# e-208_bms_master_v2.net
KiCad netlist of a schematic drawn in EAGLE
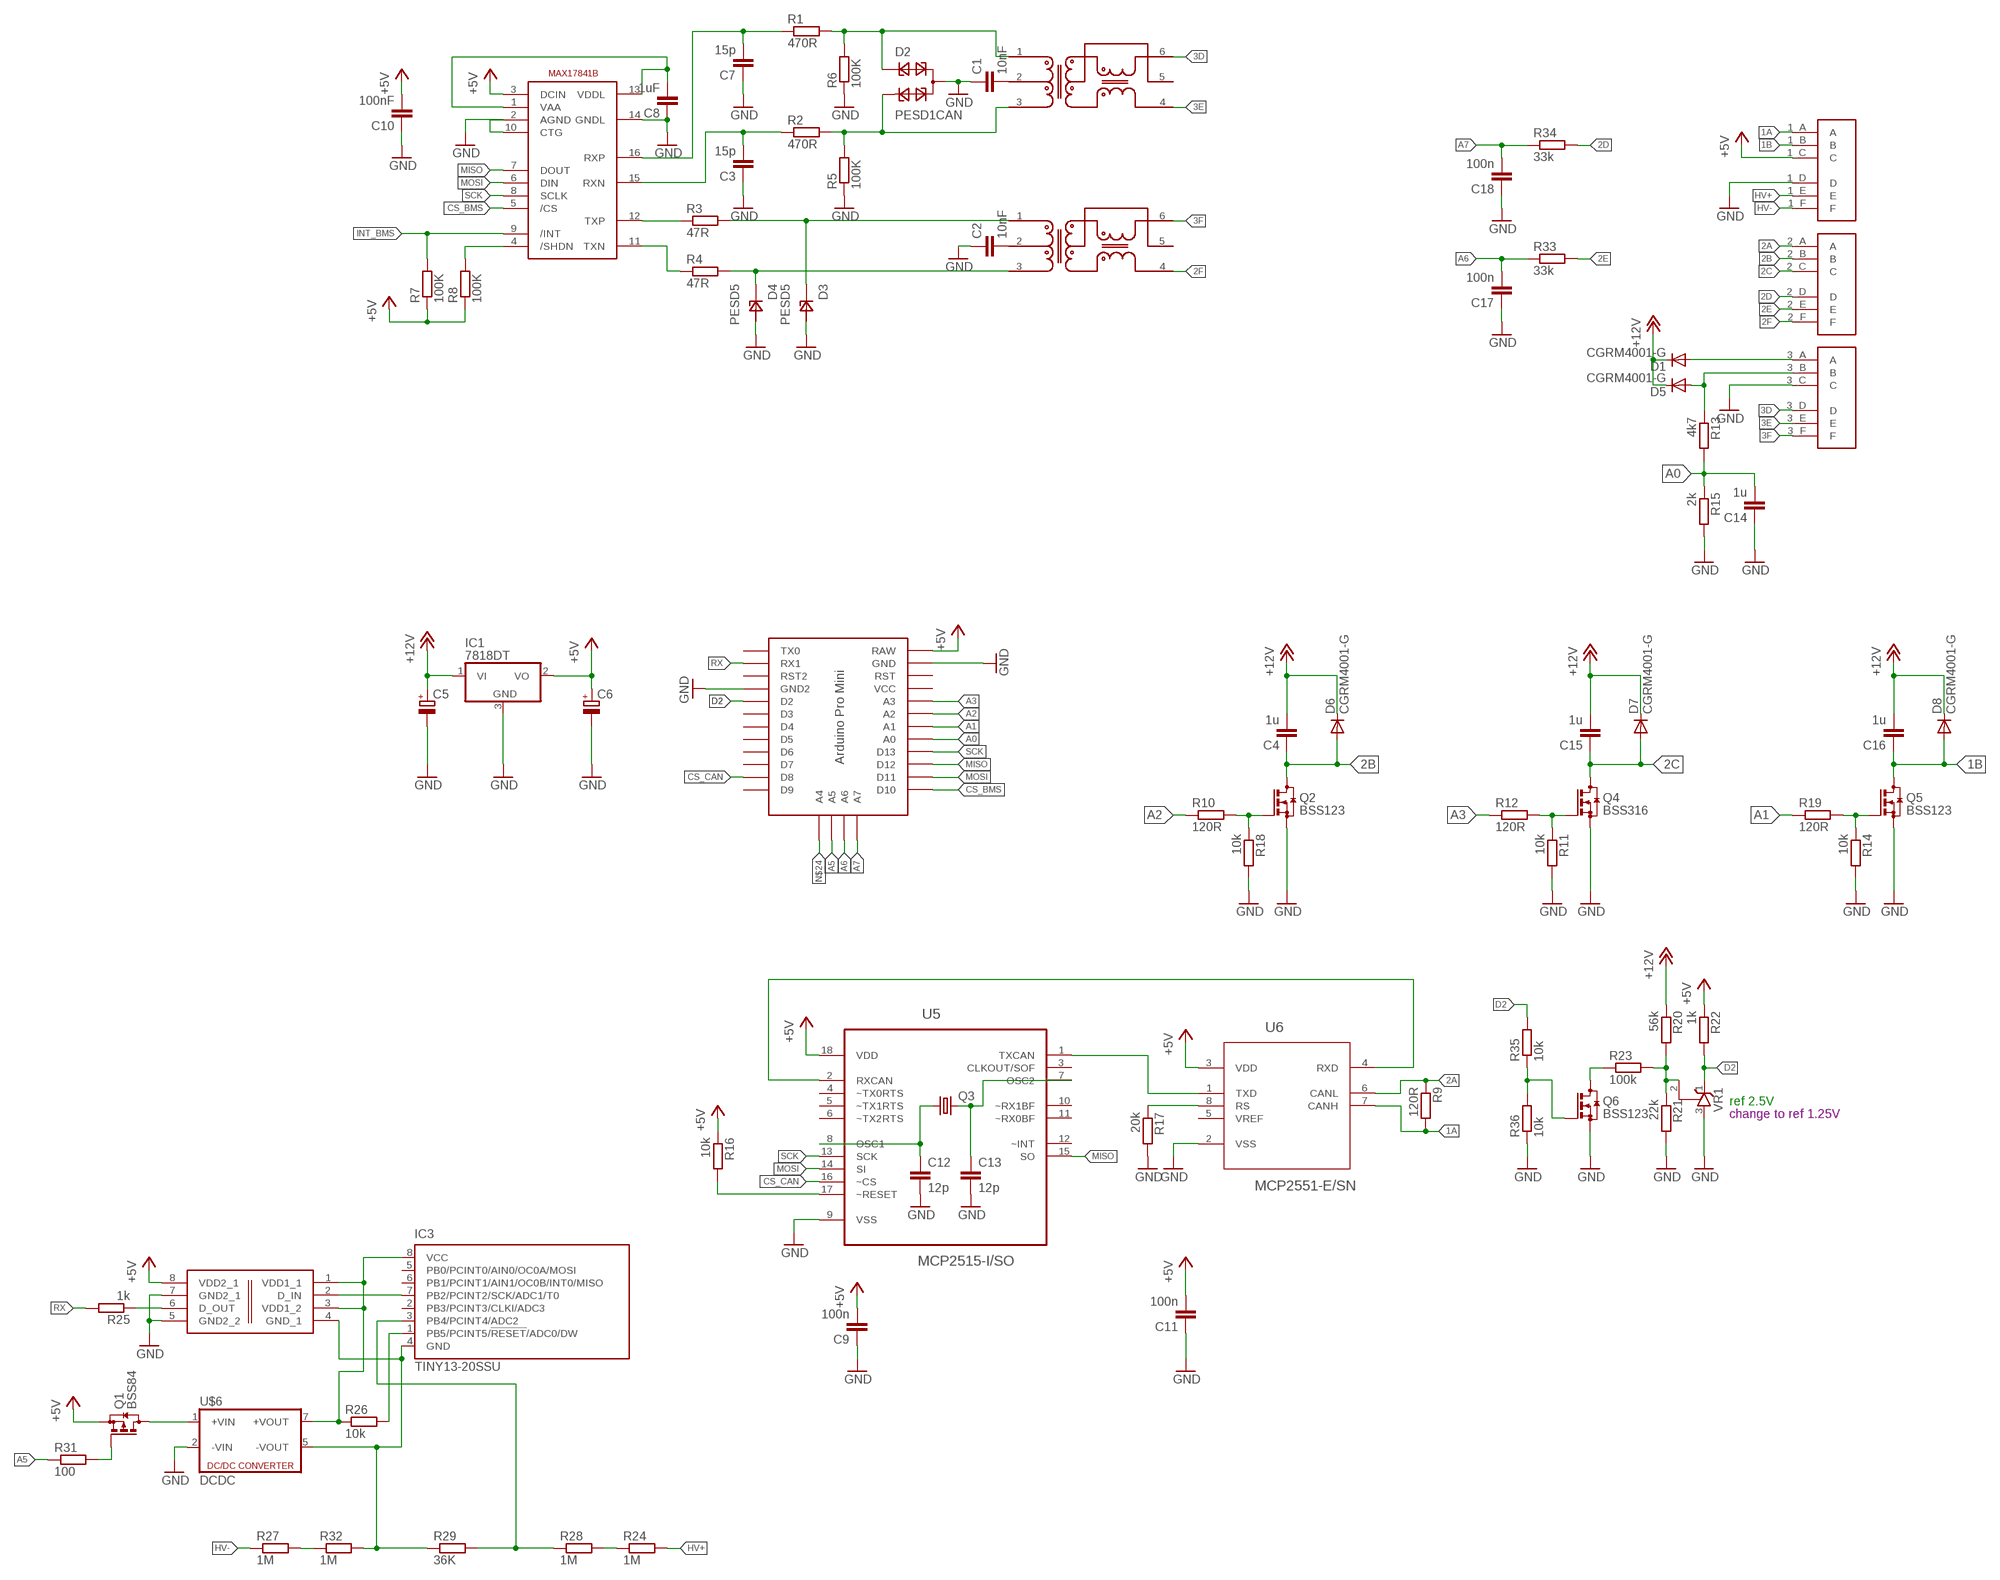
[diagram p0: schematic, sheet 1]

(export (version "E")
  (design (tool "Eeschema 10.0.6"))
  (components
    (comp (ref "C1")
      (value "10nF")
      (footprint "eagle-import:C0805")
      (libsource (lib "eagle-import") (part "C-EUC0805"))
    )
    (comp (ref "C2")
      (value "10nF")
      (footprint "eagle-import:C0805")
      (libsource (lib "eagle-import") (part "C-EUC0805"))
    )
    (comp (ref "C3")
      (value "15p")
      (footprint "eagle-import:C0805")
      (libsource (lib "eagle-import") (part "C-EUC0805"))
    )
    (comp (ref "C4")
      (value "1u")
      (footprint "eagle-import:C0805")
      (libsource (lib "eagle-import") (part "C-EUC0805"))
    )
    (comp (ref "C5")
      (value "CPOL-EU153CLV-1010")
      (footprint "eagle-import:153CLV-1010")
      (libsource (lib "eagle-import") (part "CPOL-EU153CLV-1010"))
    )
    (comp (ref "C6")
      (value "CPOL-EU153CLV-1010")
      (footprint "eagle-import:153CLV-1010")
      (libsource (lib "eagle-import") (part "CPOL-EU153CLV-1010"))
    )
    (comp (ref "C7")
      (value "15p")
      (footprint "eagle-import:C0805")
      (libsource (lib "eagle-import") (part "C-EUC0805"))
    )
    (comp (ref "C8")
      (value "1uF")
      (footprint "eagle-import:C0805")
      (libsource (lib "eagle-import") (part "C-EUC0805"))
    )
    (comp (ref "C9")
      (value "100n")
      (footprint "eagle-import:C0805")
      (libsource (lib "eagle-import") (part "C-EUC0805"))
    )
    (comp (ref "C10")
      (value "100nF")
      (footprint "eagle-import:C0805")
      (libsource (lib "eagle-import") (part "C-EUC0805"))
    )
    (comp (ref "C11")
      (value "100n")
      (footprint "eagle-import:C0805")
      (libsource (lib "eagle-import") (part "C-EUC0805"))
    )
    (comp (ref "C12")
      (value "12p")
      (footprint "eagle-import:C0603")
      (libsource (lib "eagle-import") (part "C-EUC0603"))
    )
    (comp (ref "C13")
      (value "12p")
      (footprint "eagle-import:C0603")
      (libsource (lib "eagle-import") (part "C-EUC0603"))
    )
    (comp (ref "C14")
      (value "1u")
      (footprint "eagle-import:C0805")
      (libsource (lib "eagle-import") (part "C-EUC0805"))
    )
    (comp (ref "C15")
      (value "1u")
      (footprint "eagle-import:C0805")
      (libsource (lib "eagle-import") (part "C-EUC0805"))
    )
    (comp (ref "C16")
      (value "1u")
      (footprint "eagle-import:C0805")
      (libsource (lib "eagle-import") (part "C-EUC0805"))
    )
    (comp (ref "C17")
      (value "100n")
      (footprint "eagle-import:C0805")
      (libsource (lib "eagle-import") (part "C-EUC0805"))
    )
    (comp (ref "C18")
      (value "100n")
      (footprint "eagle-import:C0805")
      (libsource (lib "eagle-import") (part "C-EUC0805"))
    )
    (comp (ref "D1")
      (value "CGRM4001-G")
      (footprint "eagle-import:SOD-123_MINI-SMA")
      (libsource (lib "eagle-import") (part "CGRM400-G1"))
    )
    (comp (ref "D2")
      (value "PESD1CAN")
      (footprint "eagle-import:SOT23")
      (libsource (lib "eagle-import") (part "PESD1CAN"))
    )
    (comp (ref "D3")
      (value "PESD5")
      (footprint "eagle-import:SOD323")
      (libsource (lib "eagle-import") (part "PESD5"))
    )
    (comp (ref "D4")
      (value "PESD5")
      (footprint "eagle-import:SOD323")
      (libsource (lib "eagle-import") (part "PESD5"))
    )
    (comp (ref "D5")
      (value "CGRM4001-G")
      (footprint "eagle-import:SOD-123_MINI-SMA")
      (libsource (lib "eagle-import") (part "CGRM400-G1"))
    )
    (comp (ref "D6")
      (value "CGRM4001-G")
      (footprint "eagle-import:SOD-123_MINI-SMA")
      (libsource (lib "eagle-import") (part "CGRM400-G1"))
    )
    (comp (ref "D7")
      (value "CGRM4001-G")
      (footprint "eagle-import:SOD-123_MINI-SMA")
      (libsource (lib "eagle-import") (part "CGRM400-G1"))
    )
    (comp (ref "D8")
      (value "CGRM4001-G")
      (footprint "eagle-import:SOD-123_MINI-SMA")
      (libsource (lib "eagle-import") (part "CGRM400-G1"))
    )
    (comp (ref "IC1")
      (value "7818DT")
      (footprint "eagle-import:TO252")
      (libsource (lib "eagle-import") (part "78DT18"))
    )
    (comp (ref "IC3")
      (value "TINY13-20SSU")
      (footprint "eagle-import:8S1")
      (fields (field (name "MPN") "ATTINY13-20SSU"))
      (libsource (lib "eagle-import") (part "TINY13SSU-20"))
    )
    (comp (ref "Q1")
      (value "BSS84")
      (footprint "eagle-import:SOT23")
      (libsource (lib "eagle-import") (part "BSS84"))
    )
    (comp (ref "Q2")
      (value "BSS123")
      (footprint "eagle-import:SOT23")
      (libsource (lib "eagle-import") (part "BSS123"))
    )
    (comp (ref "Q3")
      (value "CRYSTALHC49U-V")
      (footprint "eagle-import:HC49U-V")
      (libsource (lib "eagle-import") (part "CRYSTALHC49U-V"))
    )
    (comp (ref "Q4")
      (value "BSS316")
      (footprint "eagle-import:SOT23")
      (libsource (lib "eagle-import") (part "BSS123"))
    )
    (comp (ref "Q5")
      (value "BSS123")
      (footprint "eagle-import:SOT23")
      (libsource (lib "eagle-import") (part "BSS123"))
    )
    (comp (ref "Q6")
      (value "BSS123")
      (footprint "eagle-import:SOT23")
      (libsource (lib "eagle-import") (part "BSS123"))
    )
    (comp (ref "R1")
      (value "470R")
      (footprint "eagle-import:R0805")
      (libsource (lib "eagle-import") (part "R-EU_R0805"))
    )
    (comp (ref "R2")
      (value "470R")
      (footprint "eagle-import:R0805")
      (libsource (lib "eagle-import") (part "R-EU_R0805"))
    )
    (comp (ref "R3")
      (value "47R")
      (footprint "eagle-import:R0805")
      (libsource (lib "eagle-import") (part "R-EU_R0805"))
    )
    (comp (ref "R4")
      (value "47R")
      (footprint "eagle-import:R0805")
      (libsource (lib "eagle-import") (part "R-EU_R0805"))
    )
    (comp (ref "R5")
      (value "100K")
      (footprint "eagle-import:R0805")
      (libsource (lib "eagle-import") (part "R-EU_R0805"))
    )
    (comp (ref "R6")
      (value "100K")
      (footprint "eagle-import:R0805")
      (libsource (lib "eagle-import") (part "R-EU_R0805"))
    )
    (comp (ref "R7")
      (value "100K")
      (footprint "eagle-import:R0805")
      (libsource (lib "eagle-import") (part "R-EU_R0805"))
    )
    (comp (ref "R8")
      (value "100K")
      (footprint "eagle-import:R0805")
      (libsource (lib "eagle-import") (part "R-EU_R0805"))
    )
    (comp (ref "R9")
      (value "120R")
      (footprint "eagle-import:R0805")
      (libsource (lib "eagle-import") (part "R-EU_R0805"))
    )
    (comp (ref "R10")
      (value "120R")
      (footprint "eagle-import:R0805")
      (libsource (lib "eagle-import") (part "R-EU_R0805"))
    )
    (comp (ref "R11")
      (value "10k")
      (footprint "eagle-import:R0805")
      (libsource (lib "eagle-import") (part "R-EU_R0805"))
    )
    (comp (ref "R12")
      (value "120R")
      (footprint "eagle-import:R0805")
      (libsource (lib "eagle-import") (part "R-EU_R0805"))
    )
    (comp (ref "R13")
      (value "4k7")
      (footprint "eagle-import:R0805")
      (libsource (lib "eagle-import") (part "R-EU_R0805"))
    )
    (comp (ref "R14")
      (value "10k")
      (footprint "eagle-import:R0805")
      (libsource (lib "eagle-import") (part "R-EU_R0805"))
    )
    (comp (ref "R15")
      (value "2k")
      (footprint "eagle-import:R0805")
      (libsource (lib "eagle-import") (part "R-EU_R0805"))
    )
    (comp (ref "R16")
      (value "10k")
      (footprint "eagle-import:R0805")
      (libsource (lib "eagle-import") (part "R-EU_R0805"))
    )
    (comp (ref "R17")
      (value "20k")
      (footprint "eagle-import:R0805")
      (libsource (lib "eagle-import") (part "R-EU_R0805"))
    )
    (comp (ref "R18")
      (value "10k")
      (footprint "eagle-import:R0805")
      (libsource (lib "eagle-import") (part "R-EU_R0805"))
    )
    (comp (ref "R19")
      (value "120R")
      (footprint "eagle-import:R0805")
      (libsource (lib "eagle-import") (part "R-EU_R0805"))
    )
    (comp (ref "R20")
      (value "56k")
      (footprint "eagle-import:R0805")
      (libsource (lib "eagle-import") (part "R-EU_R0805"))
    )
    (comp (ref "R21")
      (value "22k")
      (footprint "eagle-import:R0805")
      (libsource (lib "eagle-import") (part "R-EU_R0805"))
    )
    (comp (ref "R22")
      (value "1k")
      (footprint "eagle-import:R0805")
      (libsource (lib "eagle-import") (part "R-EU_R0805"))
    )
    (comp (ref "R23")
      (value "100k")
      (footprint "eagle-import:R0805")
      (libsource (lib "eagle-import") (part "R-EU_R0805"))
    )
    (comp (ref "R24")
      (value "1M")
      (footprint "eagle-import:R0805")
      (libsource (lib "eagle-import") (part "R-EU_R0805"))
    )
    (comp (ref "R25")
      (value "1k")
      (footprint "eagle-import:R0805")
      (libsource (lib "eagle-import") (part "R-EU_R0805"))
    )
    (comp (ref "R26")
      (value "10k")
      (footprint "eagle-import:R0805")
      (libsource (lib "eagle-import") (part "R-EU_R0805"))
    )
    (comp (ref "R27")
      (value "1M")
      (footprint "eagle-import:R0805")
      (libsource (lib "eagle-import") (part "R-EU_R0805"))
    )
    (comp (ref "R28")
      (value "1M")
      (footprint "eagle-import:R0805")
      (libsource (lib "eagle-import") (part "R-EU_R0805"))
    )
    (comp (ref "R29")
      (value "36K")
      (footprint "eagle-import:R0805")
      (libsource (lib "eagle-import") (part "R-EU_R0805"))
    )
    (comp (ref "R31")
      (value "100")
      (footprint "eagle-import:R0805")
      (libsource (lib "eagle-import") (part "R-EU_R0805"))
    )
    (comp (ref "R32")
      (value "1M")
      (footprint "eagle-import:R0805")
      (libsource (lib "eagle-import") (part "R-EU_R0805"))
    )
    (comp (ref "R33")
      (value "33k")
      (footprint "eagle-import:R0805")
      (libsource (lib "eagle-import") (part "R-EU_R0805"))
    )
    (comp (ref "R34")
      (value "33k")
      (footprint "eagle-import:R0805")
      (libsource (lib "eagle-import") (part "R-EU_R0805"))
    )
    (comp (ref "R35")
      (value "10k")
      (footprint "eagle-import:R0805")
      (libsource (lib "eagle-import") (part "R-EU_R0805"))
    )
    (comp (ref "R36")
      (value "10k")
      (footprint "eagle-import:R0805")
      (libsource (lib "eagle-import") (part "R-EU_R0805"))
    )
    (comp (ref "U$1")
      (value "18P_ME")
      (footprint "eagle-import:18P_ME")
      (libsource (lib "eagle-import") (part "18P_ME"))
    )
    (comp (ref "U$2")
      (value "PRO-MINI-3")
      (footprint "eagle-import:PRO-MINI-3")
      (libsource (lib "eagle-import") (part "PRO-MINI-3"))
    )
    (comp (ref "U$3")
      (value "SM91502ALE")
      (footprint "eagle-import:SM91502ALE")
      (libsource (lib "eagle-import") (part "SM91502ALE"))
    )
    (comp (ref "U$4")
      (value "SM91502ALE")
      (footprint "eagle-import:SM91502ALE")
      (libsource (lib "eagle-import") (part "SM91502ALE"))
    )
    (comp (ref "U$5")
      (value "ADUM110N")
      (footprint "eagle-import:SOIC8")
      (libsource (lib "eagle-import") (part "ADUM110N"))
    )
    (comp (ref "U$6")
      (value "DCDC")
      (footprint "eagle-import:DCDC")
      (libsource (lib "eagle-import") (part "DCDC"))
    )
    (comp (ref "U2")
      (value "MAX17841B")
      (footprint "eagle-import:TSSOP16")
      (libsource (lib "eagle-import") (part "MAX17841B"))
    )
    (comp (ref "U5")
      (value "MCP2515-I/SO")
      (footprint "eagle-import:SOIC127P1034X264-18N")
      (libsource (lib "eagle-import") (part "MCP2515-I/SO"))
    )
    (comp (ref "U6")
      (value "MCP2551-E/SN")
      (footprint "eagle-import:SOIC127P600X175-8N")
      (libsource (lib "eagle-import") (part "MCP2551-E/SN"))
    )
    (comp (ref "VR1")
      (value "TL431CLPSOT23")
      (footprint "eagle-import:SOT23")
      (libsource (lib "eagle-import") (part "TL431CLPSOT23"))
    )
  )
  (nets
    (net (code "1") (name "+5V") (class "Default")
      (node (ref "C10") (pin "2") (pinfunction "2_2") (pintype "passive"))
      (node (ref "C11") (pin "2") (pinfunction "2_2") (pintype "passive"))
      (node (ref "C6") (pin "+") (pinfunction "+_+") (pintype "passive"))
      (node (ref "C9") (pin "2") (pinfunction "2_2") (pintype "passive"))
      (node (ref "IC1") (pin "2") (pinfunction "VO_2") (pintype "passive"))
      (node (ref "Q1") (pin "2") (pinfunction "S_2") (pintype "passive"))
      (node (ref "R16") (pin "1") (pinfunction "1_1") (pintype "passive"))
      (node (ref "R22") (pin "1") (pinfunction "1_1") (pintype "passive"))
      (node (ref "R7") (pin "1") (pinfunction "1_1") (pintype "passive"))
      (node (ref "R8") (pin "1") (pinfunction "1_1") (pintype "passive"))
      (node (ref "U$1") (pin "1_C") (pinfunction "C_1_C") (pintype "bidirectional"))
      (node (ref "U$2") (pin "RAW") (pinfunction "RAW_RAW") (pintype "power_in"))
      (node (ref "U$5") (pin "8") (pinfunction "VDD2_1_8") (pintype "bidirectional"))
      (node (ref "U2") (pin "3") (pinfunction "DCIN_3") (pintype "bidirectional"))
      (node (ref "U5") (pin "18") (pinfunction "VDD_18") (pintype "power_in"))
      (node (ref "U6") (pin "3") (pinfunction "VDD_3") (pintype "power_in"))
    )
    (net (code "2") (name "+12V") (class "Default")
      (node (ref "C15") (pin "2") (pinfunction "2_2") (pintype "passive"))
      (node (ref "C16") (pin "2") (pinfunction "2_2") (pintype "passive"))
      (node (ref "C4") (pin "2") (pinfunction "2_2") (pintype "passive"))
      (node (ref "C5") (pin "+") (pinfunction "+_+") (pintype "passive"))
      (node (ref "D1") (pin "C") (pinfunction "C_C") (pintype "passive"))
      (node (ref "D5") (pin "C") (pinfunction "C_C") (pintype "passive"))
      (node (ref "D6") (pin "C") (pinfunction "C_C") (pintype "passive"))
      (node (ref "D7") (pin "C") (pinfunction "C_C") (pintype "passive"))
      (node (ref "D8") (pin "C") (pinfunction "C_C") (pintype "passive"))
      (node (ref "IC1") (pin "1") (pinfunction "VI_1") (pintype "input"))
      (node (ref "R20") (pin "1") (pinfunction "1_1") (pintype "passive"))
    )
    (net (code "3") (name "1A") (class "Default")
      (node (ref "R9") (pin "2") (pinfunction "2_2") (pintype "passive"))
      (node (ref "U$1") (pin "1_A") (pinfunction "A_1_A") (pintype "bidirectional"))
      (node (ref "U6") (pin "7") (pinfunction "CANH_7") (pintype "output"))
    )
    (net (code "4") (name "1B") (class "Default")
      (node (ref "C16") (pin "1") (pinfunction "1_1") (pintype "passive"))
      (node (ref "D8") (pin "A") (pinfunction "A_A") (pintype "passive"))
      (node (ref "Q5") (pin "3") (pinfunction "D_3") (pintype "passive"))
      (node (ref "U$1") (pin "1_B") (pinfunction "B_1_B") (pintype "bidirectional"))
    )
    (net (code "5") (name "2A") (class "Default")
      (node (ref "R9") (pin "1") (pinfunction "1_1") (pintype "passive"))
      (node (ref "U$1") (pin "2_A") (pinfunction "A_2_A") (pintype "bidirectional"))
      (node (ref "U6") (pin "6") (pinfunction "CANL_6") (pintype "output"))
    )
    (net (code "6") (name "2B") (class "Default")
      (node (ref "C4") (pin "1") (pinfunction "1_1") (pintype "passive"))
      (node (ref "D6") (pin "A") (pinfunction "A_A") (pintype "passive"))
      (node (ref "Q2") (pin "3") (pinfunction "D_3") (pintype "passive"))
      (node (ref "U$1") (pin "2_B") (pinfunction "B_2_B") (pintype "bidirectional"))
    )
    (net (code "7") (name "2C") (class "Default")
      (node (ref "C15") (pin "1") (pinfunction "1_1") (pintype "passive"))
      (node (ref "D7") (pin "A") (pinfunction "A_A") (pintype "passive"))
      (node (ref "Q4") (pin "3") (pinfunction "D_3") (pintype "passive"))
      (node (ref "U$1") (pin "2_C") (pinfunction "C_2_C") (pintype "bidirectional"))
    )
    (net (code "8") (name "2D") (class "Default")
      (node (ref "R34") (pin "2") (pinfunction "2_2") (pintype "passive"))
      (node (ref "U$1") (pin "2_D") (pinfunction "D_2_D") (pintype "bidirectional"))
    )
    (net (code "9") (name "2E") (class "Default")
      (node (ref "R33") (pin "2") (pinfunction "2_2") (pintype "passive"))
      (node (ref "U$1") (pin "2_E") (pinfunction "E_2_E") (pintype "bidirectional"))
    )
    (net (code "10") (name "2F") (class "Default")
      (node (ref "U$1") (pin "2_F") (pinfunction "F_2_F") (pintype "bidirectional"))
      (node (ref "U$4") (pin "4") (pinfunction "4_4") (pintype "bidirectional"))
    )
    (net (code "11") (name "3D") (class "Default")
      (node (ref "U$1") (pin "3_D") (pinfunction "D_3_D") (pintype "bidirectional"))
      (node (ref "U$3") (pin "6") (pinfunction "6_6") (pintype "bidirectional"))
    )
    (net (code "12") (name "3E") (class "Default")
      (node (ref "U$1") (pin "3_E") (pinfunction "E_3_E") (pintype "bidirectional"))
      (node (ref "U$3") (pin "4") (pinfunction "4_4") (pintype "bidirectional"))
    )
    (net (code "13") (name "3F") (class "Default")
      (node (ref "U$1") (pin "3_F") (pinfunction "F_3_F") (pintype "bidirectional"))
      (node (ref "U$4") (pin "6") (pinfunction "6_6") (pintype "bidirectional"))
    )
    (net (code "14") (name "A0") (class "Default")
      (node (ref "C14") (pin "2") (pinfunction "2_2") (pintype "passive"))
      (node (ref "R13") (pin "2") (pinfunction "2_2") (pintype "passive"))
      (node (ref "R15") (pin "1") (pinfunction "1_1") (pintype "passive"))
      (node (ref "U$2") (pin "A0") (pinfunction "A0_A0") (pintype "bidirectional"))
    )
    (net (code "15") (name "A1") (class "Default")
      (node (ref "R19") (pin "1") (pinfunction "1_1") (pintype "passive"))
      (node (ref "U$2") (pin "A1") (pinfunction "A1_A1") (pintype "bidirectional"))
    )
    (net (code "16") (name "A2") (class "Default")
      (node (ref "R10") (pin "1") (pinfunction "1_1") (pintype "passive"))
      (node (ref "U$2") (pin "A2") (pinfunction "A2_A2") (pintype "bidirectional"))
    )
    (net (code "17") (name "A3") (class "Default")
      (node (ref "R12") (pin "1") (pinfunction "1_1") (pintype "passive"))
      (node (ref "U$2") (pin "A3") (pinfunction "A3_A3") (pintype "bidirectional"))
    )
    (net (code "18") (name "A5") (class "Default")
      (node (ref "R31") (pin "1") (pinfunction "1_1") (pintype "passive"))
      (node (ref "U$2") (pin "A5") (pinfunction "A5_A5") (pintype "bidirectional"))
    )
    (net (code "19") (name "A6") (class "Default")
      (node (ref "C17") (pin "2") (pinfunction "2_2") (pintype "passive"))
      (node (ref "R33") (pin "1") (pinfunction "1_1") (pintype "passive"))
      (node (ref "U$2") (pin "A6") (pinfunction "A6_A6") (pintype "bidirectional"))
    )
    (net (code "20") (name "A7") (class "Default")
      (node (ref "C18") (pin "2") (pinfunction "2_2") (pintype "passive"))
      (node (ref "R34") (pin "1") (pinfunction "1_1") (pintype "passive"))
      (node (ref "U$2") (pin "A7") (pinfunction "A7_A7") (pintype "bidirectional"))
    )
    (net (code "21") (name "CS_BMS") (class "Default")
      (node (ref "U$2") (pin "D10") (pinfunction "D10_D10") (pintype "bidirectional"))
      (node (ref "U2") (pin "5") (pinfunction "/CS_5") (pintype "bidirectional"))
    )
    (net (code "22") (name "CS_CAN") (class "Default")
      (node (ref "U$2") (pin "D8") (pinfunction "D8_D8") (pintype "bidirectional"))
      (node (ref "U5") (pin "16") (pinfunction "~{CS}_16") (pintype "input"))
    )
    (net (code "23") (name "D2") (class "Default")
      (node (ref "R22") (pin "2") (pinfunction "2_2") (pintype "passive"))
      (node (ref "R35") (pin "2") (pinfunction "2_2") (pintype "passive"))
      (node (ref "U$2") (pin "D2") (pinfunction "D2_D2") (pintype "bidirectional"))
      (node (ref "VR1") (pin "1") (pinfunction "C_1") (pintype "passive"))
    )
    (net (code "24") (name "GND") (class "Default")
      (node (ref "C1") (pin "1") (pinfunction "1_1") (pintype "passive"))
      (node (ref "C10") (pin "1") (pinfunction "1_1") (pintype "passive"))
      (node (ref "C11") (pin "1") (pinfunction "1_1") (pintype "passive"))
      (node (ref "C12") (pin "2") (pinfunction "2_2") (pintype "passive"))
      (node (ref "C13") (pin "2") (pinfunction "2_2") (pintype "passive"))
      (node (ref "C14") (pin "1") (pinfunction "1_1") (pintype "passive"))
      (node (ref "C17") (pin "1") (pinfunction "1_1") (pintype "passive"))
      (node (ref "C18") (pin "1") (pinfunction "1_1") (pintype "passive"))
      (node (ref "C2") (pin "1") (pinfunction "1_1") (pintype "passive"))
      (node (ref "C3") (pin "1") (pinfunction "1_1") (pintype "passive"))
      (node (ref "C5") (pin "-") (pinfunction "-_-") (pintype "passive"))
      (node (ref "C6") (pin "-") (pinfunction "-_-") (pintype "passive"))
      (node (ref "C7") (pin "1") (pinfunction "1_1") (pintype "passive"))
      (node (ref "C8") (pin "1") (pinfunction "1_1") (pintype "passive"))
      (node (ref "C9") (pin "1") (pinfunction "1_1") (pintype "passive"))
      (node (ref "D2") (pin "3") (pinfunction "3_3") (pintype "passive"))
      (node (ref "D3") (pin "2") (pinfunction "2_2") (pintype "passive"))
      (node (ref "D4") (pin "2") (pinfunction "2_2") (pintype "passive"))
      (node (ref "IC1") (pin "3") (pinfunction "GND_3") (pintype "passive"))
      (node (ref "Q2") (pin "2") (pinfunction "S_2") (pintype "passive"))
      (node (ref "Q4") (pin "2") (pinfunction "S_2") (pintype "passive"))
      (node (ref "Q5") (pin "2") (pinfunction "S_2") (pintype "passive"))
      (node (ref "Q6") (pin "2") (pinfunction "S_2") (pintype "passive"))
      (node (ref "R11") (pin "2") (pinfunction "2_2") (pintype "passive"))
      (node (ref "R14") (pin "2") (pinfunction "2_2") (pintype "passive"))
      (node (ref "R15") (pin "2") (pinfunction "2_2") (pintype "passive"))
      (node (ref "R17") (pin "2") (pinfunction "2_2") (pintype "passive"))
      (node (ref "R18") (pin "2") (pinfunction "2_2") (pintype "passive"))
      (node (ref "R21") (pin "2") (pinfunction "2_2") (pintype "passive"))
      (node (ref "R36") (pin "1") (pinfunction "1_1") (pintype "passive"))
      (node (ref "R5") (pin "1") (pinfunction "1_1") (pintype "passive"))
      (node (ref "R6") (pin "1") (pinfunction "1_1") (pintype "passive"))
      (node (ref "U$1") (pin "1_D") (pinfunction "D_1_D") (pintype "bidirectional"))
      (node (ref "U$1") (pin "3_C") (pinfunction "C_3_C") (pintype "bidirectional"))
      (node (ref "U$2") (pin "GND") (pinfunction "GND_GND") (pintype "input"))
      (node (ref "U$2") (pin "GND1") (pinfunction "GND2_GND1") (pintype "bidirectional"))
      (node (ref "U$5") (pin "5") (pinfunction "GND2_2_5") (pintype "bidirectional"))
      (node (ref "U$5") (pin "7") (pinfunction "GND2_1_7") (pintype "bidirectional"))
      (node (ref "U$6") (pin "2") (pinfunction "-VIN_2") (pintype "passive"))
      (node (ref "U2") (pin "10") (pinfunction "CTG_10") (pintype "bidirectional"))
      (node (ref "U2") (pin "14") (pinfunction "GNDL_14") (pintype "bidirectional"))
      (node (ref "U2") (pin "2") (pinfunction "AGND_2") (pintype "bidirectional"))
      (node (ref "U5") (pin "9") (pinfunction "VSS_9") (pintype "power_in"))
      (node (ref "U6") (pin "2") (pinfunction "VSS_2") (pintype "power_in"))
      (node (ref "VR1") (pin "3") (pinfunction "A_3") (pintype "passive"))
    )
    (net (code "25") (name "HV+") (class "Default")
      (node (ref "R24") (pin "2") (pinfunction "2_2") (pintype "passive"))
      (node (ref "U$1") (pin "1_E") (pinfunction "E_1_E") (pintype "bidirectional"))
    )
    (net (code "26") (name "HV-") (class "Default")
      (node (ref "R27") (pin "1") (pinfunction "1_1") (pintype "passive"))
      (node (ref "U$1") (pin "1_F") (pinfunction "F_1_F") (pintype "bidirectional"))
    )
    (net (code "27") (name "INT_BMS") (class "Default")
      (node (ref "R7") (pin "2") (pinfunction "2_2") (pintype "passive"))
      (node (ref "U2") (pin "9") (pinfunction "/INT_9") (pintype "bidirectional"))
    )
    (net (code "28") (name "MISO") (class "Default")
      (node (ref "U$2") (pin "D12") (pinfunction "D12_D12") (pintype "bidirectional"))
      (node (ref "U2") (pin "7") (pinfunction "DOUT_7") (pintype "bidirectional"))
      (node (ref "U5") (pin "15") (pinfunction "SO_15") (pintype "output"))
    )
    (net (code "29") (name "MOSI") (class "Default")
      (node (ref "U$2") (pin "D11") (pinfunction "D11_D11") (pintype "bidirectional"))
      (node (ref "U2") (pin "6") (pinfunction "DIN_6") (pintype "bidirectional"))
      (node (ref "U5") (pin "14") (pinfunction "SI_14") (pintype "input"))
    )
    (net (code "30") (name "N$24") (class "Default")
      (node (ref "U$2") (pin "A4") (pinfunction "A4_A4") (pintype "bidirectional"))
    )
    (net (code "31") (name "Net-(C1-Pad2)") (class "Default")
      (node (ref "C1") (pin "2") (pinfunction "2_2") (pintype "passive"))
      (node (ref "U$3") (pin "2") (pinfunction "2_2") (pintype "bidirectional"))
    )
    (net (code "32") (name "Net-(C2-Pad2)") (class "Default")
      (node (ref "C2") (pin "2") (pinfunction "2_2") (pintype "passive"))
      (node (ref "U$4") (pin "2") (pinfunction "2_2") (pintype "bidirectional"))
    )
    (net (code "33") (name "Net-(D2-Pad1)") (class "Default")
      (node (ref "D2") (pin "1") (pinfunction "1_1") (pintype "passive"))
      (node (ref "R1") (pin "2") (pinfunction "2_2") (pintype "passive"))
      (node (ref "R6") (pin "2") (pinfunction "2_2") (pintype "passive"))
      (node (ref "U$3") (pin "1") (pinfunction "1_1") (pintype "bidirectional"))
    )
    (net (code "34") (name "Net-(D2-Pad2)") (class "Default")
      (node (ref "D2") (pin "2") (pinfunction "2_2") (pintype "passive"))
      (node (ref "R2") (pin "2") (pinfunction "2_2") (pintype "passive"))
      (node (ref "R5") (pin "2") (pinfunction "2_2") (pintype "passive"))
      (node (ref "U$3") (pin "3") (pinfunction "3_3") (pintype "bidirectional"))
    )
    (net (code "35") (name "Net-(D3-Pad1)") (class "Default")
      (node (ref "D3") (pin "1") (pinfunction "1_1") (pintype "passive"))
      (node (ref "R3") (pin "2") (pinfunction "2_2") (pintype "passive"))
      (node (ref "U$4") (pin "1") (pinfunction "1_1") (pintype "bidirectional"))
    )
    (net (code "36") (name "Net-(D4-Pad1)") (class "Default")
      (node (ref "D4") (pin "1") (pinfunction "1_1") (pintype "passive"))
      (node (ref "R4") (pin "2") (pinfunction "2_2") (pintype "passive"))
      (node (ref "U$4") (pin "3") (pinfunction "3_3") (pintype "bidirectional"))
    )
    (net (code "37") (name "Net-(IC3-GND)") (class "Default")
      (node (ref "IC3") (pin "4") (pinfunction "GND_4") (pintype "power_in"))
      (node (ref "R29") (pin "1") (pinfunction "1_1") (pintype "passive"))
      (node (ref "R32") (pin "2") (pinfunction "2_2") (pintype "passive"))
      (node (ref "U$5") (pin "4") (pinfunction "GND_1_4") (pintype "bidirectional"))
      (node (ref "U$6") (pin "5") (pinfunction "-VOUT_5") (pintype "passive"))
    )
    (net (code "38") (name "Net-(IC3-PB2{slash}PCINT2{slash}SCK{slash}ADC1{slash}T0)") (class "Default")
      (node (ref "IC3") (pin "7") (pinfunction "PB2/PCINT2/SCK/ADC1/T0_7") (pintype "bidirectional"))
      (node (ref "U$5") (pin "2") (pinfunction "D_IN_2") (pintype "bidirectional"))
    )
    (net (code "39") (name "Net-(IC3-PB4{slash}PCINT4{slash}ADC2)") (class "Default")
      (node (ref "IC3") (pin "3") (pinfunction "PB4/PCINT4/ADC2_3") (pintype "bidirectional"))
      (node (ref "R28") (pin "1") (pinfunction "1_1") (pintype "passive"))
      (node (ref "R29") (pin "2") (pinfunction "2_2") (pintype "passive"))
    )
    (net (code "40") (name "Net-(IC3-PB5{slash}PCINT5{slash}~{RESET}{slash}ADC0{slash}DW)") (class "Default")
      (node (ref "IC3") (pin "1") (pinfunction "PB5/PCINT5/~{RESET}/ADC0/DW_1") (pintype "bidirectional"))
      (node (ref "R26") (pin "2") (pinfunction "2_2") (pintype "passive"))
    )
    (net (code "41") (name "Net-(IC3-VCC)") (class "Default")
      (node (ref "IC3") (pin "8") (pinfunction "VCC_8") (pintype "power_in"))
      (node (ref "R26") (pin "1") (pinfunction "1_1") (pintype "passive"))
      (node (ref "U$5") (pin "1") (pinfunction "VDD1_1_1") (pintype "bidirectional"))
      (node (ref "U$5") (pin "3") (pinfunction "VDD1_2_3") (pintype "bidirectional"))
      (node (ref "U$6") (pin "7") (pinfunction "+VOUT_7") (pintype "passive"))
    )
    (net (code "42") (name "Net-(Q1-D)") (class "Default")
      (node (ref "Q1") (pin "3") (pinfunction "D_3") (pintype "passive"))
      (node (ref "U$6") (pin "1") (pinfunction "+VIN_1") (pintype "passive"))
    )
    (net (code "43") (name "Net-(Q1-G)") (class "Default")
      (node (ref "Q1") (pin "1") (pinfunction "G_1") (pintype "passive"))
      (node (ref "R31") (pin "2") (pinfunction "2_2") (pintype "passive"))
    )
    (net (code "44") (name "Net-(Q2-G)") (class "Default")
      (node (ref "Q2") (pin "1") (pinfunction "G_1") (pintype "passive"))
      (node (ref "R10") (pin "2") (pinfunction "2_2") (pintype "passive"))
      (node (ref "R18") (pin "1") (pinfunction "1_1") (pintype "passive"))
    )
    (net (code "45") (name "Net-(Q4-G)") (class "Default")
      (node (ref "Q4") (pin "1") (pinfunction "G_1") (pintype "passive"))
      (node (ref "R11") (pin "1") (pinfunction "1_1") (pintype "passive"))
      (node (ref "R12") (pin "2") (pinfunction "2_2") (pintype "passive"))
    )
    (net (code "46") (name "Net-(Q5-G)") (class "Default")
      (node (ref "Q5") (pin "1") (pinfunction "G_1") (pintype "passive"))
      (node (ref "R14") (pin "1") (pinfunction "1_1") (pintype "passive"))
      (node (ref "R19") (pin "2") (pinfunction "2_2") (pintype "passive"))
    )
    (net (code "47") (name "Net-(Q6-D)") (class "Default")
      (node (ref "Q6") (pin "3") (pinfunction "D_3") (pintype "passive"))
      (node (ref "R23") (pin "1") (pinfunction "1_1") (pintype "passive"))
    )
    (net (code "48") (name "Net-(Q6-G)") (class "Default")
      (node (ref "Q6") (pin "1") (pinfunction "G_1") (pintype "passive"))
      (node (ref "R35") (pin "1") (pinfunction "1_1") (pintype "passive"))
      (node (ref "R36") (pin "2") (pinfunction "2_2") (pintype "passive"))
    )
    (net (code "49") (name "Net-(R24-Pad1)") (class "Default")
      (node (ref "R24") (pin "1") (pinfunction "1_1") (pintype "passive"))
      (node (ref "R28") (pin "2") (pinfunction "2_2") (pintype "passive"))
    )
    (net (code "50") (name "Net-(R27-Pad2)") (class "Default")
      (node (ref "R27") (pin "2") (pinfunction "2_2") (pintype "passive"))
      (node (ref "R32") (pin "1") (pinfunction "1_1") (pintype "passive"))
    )
    (net (code "51") (name "Net-(U$1C-A)") (class "Default")
      (node (ref "D1") (pin "A") (pinfunction "A_A") (pintype "passive"))
      (node (ref "U$1") (pin "3_A") (pinfunction "A_3_A") (pintype "bidirectional"))
    )
    (net (code "52") (name "Net-(U$1C-B)") (class "Default")
      (node (ref "D5") (pin "A") (pinfunction "A_A") (pintype "passive"))
      (node (ref "R13") (pin "1") (pinfunction "1_1") (pintype "passive"))
      (node (ref "U$1") (pin "3_B") (pinfunction "B_3_B") (pintype "bidirectional"))
    )
    (net (code "53") (name "Net-(U$5-D_OUT)") (class "Default")
      (node (ref "R25") (pin "1") (pinfunction "1_1") (pintype "passive"))
      (node (ref "U$5") (pin "6") (pinfunction "D_OUT_6") (pintype "bidirectional"))
    )
    (net (code "54") (name "Net-(U2-RXN)") (class "Default")
      (node (ref "C3") (pin "2") (pinfunction "2_2") (pintype "passive"))
      (node (ref "R2") (pin "1") (pinfunction "1_1") (pintype "passive"))
      (node (ref "U2") (pin "15") (pinfunction "RXN_15") (pintype "bidirectional"))
    )
    (net (code "55") (name "Net-(U2-RXP)") (class "Default")
      (node (ref "C7") (pin "2") (pinfunction "2_2") (pintype "passive"))
      (node (ref "R1") (pin "1") (pinfunction "1_1") (pintype "passive"))
      (node (ref "U2") (pin "16") (pinfunction "RXP_16") (pintype "bidirectional"))
    )
    (net (code "56") (name "Net-(U2-TXN)") (class "Default")
      (node (ref "R4") (pin "1") (pinfunction "1_1") (pintype "passive"))
      (node (ref "U2") (pin "11") (pinfunction "TXN_11") (pintype "bidirectional"))
    )
    (net (code "57") (name "Net-(U2-TXP)") (class "Default")
      (node (ref "R3") (pin "1") (pinfunction "1_1") (pintype "passive"))
      (node (ref "U2") (pin "12") (pinfunction "TXP_12") (pintype "bidirectional"))
    )
    (net (code "58") (name "Net-(U2-VAA)") (class "Default")
      (node (ref "C8") (pin "2") (pinfunction "2_2") (pintype "passive"))
      (node (ref "U2") (pin "1") (pinfunction "VAA_1") (pintype "bidirectional"))
      (node (ref "U2") (pin "13") (pinfunction "VDDL_13") (pintype "bidirectional"))
    )
    (net (code "59") (name "Net-(U2-{slash}SHDN)") (class "Default")
      (node (ref "R8") (pin "2") (pinfunction "2_2") (pintype "passive"))
      (node (ref "U2") (pin "4") (pinfunction "/SHDN_4") (pintype "bidirectional"))
    )
    (net (code "60") (name "Net-(U5-OSC1)") (class "Default")
      (node (ref "C12") (pin "1") (pinfunction "1_1") (pintype "passive"))
      (node (ref "Q3") (pin "1") (pinfunction "1_1") (pintype "passive"))
      (node (ref "U5") (pin "8") (pinfunction "OSC1_8") (pintype "input"))
    )
    (net (code "61") (name "Net-(U5-OSC2)") (class "Default")
      (node (ref "C13") (pin "1") (pinfunction "1_1") (pintype "passive"))
      (node (ref "Q3") (pin "2") (pinfunction "2_2") (pintype "passive"))
      (node (ref "U5") (pin "7") (pinfunction "OSC2_7") (pintype "output"))
    )
    (net (code "62") (name "Net-(U5-RXCAN)") (class "Default")
      (node (ref "U5") (pin "2") (pinfunction "RXCAN_2") (pintype "input"))
      (node (ref "U6") (pin "4") (pinfunction "RXD_4") (pintype "output"))
    )
    (net (code "63") (name "Net-(U5-TXCAN)") (class "Default")
      (node (ref "U5") (pin "1") (pinfunction "TXCAN_1") (pintype "output"))
      (node (ref "U6") (pin "1") (pinfunction "TXD_1") (pintype "input"))
    )
    (net (code "64") (name "Net-(U5-~{RESET})") (class "Default")
      (node (ref "R16") (pin "2") (pinfunction "2_2") (pintype "passive"))
      (node (ref "U5") (pin "17") (pinfunction "~{RESET}_17") (pintype "input"))
    )
    (net (code "65") (name "Net-(U6-RS)") (class "Default")
      (node (ref "R17") (pin "1") (pinfunction "1_1") (pintype "passive"))
      (node (ref "U6") (pin "8") (pinfunction "RS_8") (pintype "input"))
    )
    (net (code "66") (name "Net-(VR1-R)") (class "Default")
      (node (ref "R20") (pin "2") (pinfunction "2_2") (pintype "passive"))
      (node (ref "R21") (pin "1") (pinfunction "1_1") (pintype "passive"))
      (node (ref "R23") (pin "2") (pinfunction "2_2") (pintype "passive"))
      (node (ref "VR1") (pin "2") (pinfunction "R_2") (pintype "passive"))
    )
    (net (code "67") (name "RX") (class "Default")
      (node (ref "R25") (pin "2") (pinfunction "2_2") (pintype "passive"))
      (node (ref "U$2") (pin "RX1") (pinfunction "RX1_RX1") (pintype "bidirectional"))
    )
    (net (code "68") (name "SCK") (class "Default")
      (node (ref "U$2") (pin "D13") (pinfunction "D13_D13") (pintype "bidirectional"))
      (node (ref "U2") (pin "8") (pinfunction "SCLK_8") (pintype "bidirectional"))
      (node (ref "U5") (pin "13") (pinfunction "SCK_13") (pintype "input"))
    )
    (net (code "69") (name "unconnected-(IC3-PB0{slash}PCINT0{slash}AIN0{slash}OC0A{slash}MOSI-Pad5)") (class "Default")
      (node (ref "IC3") (pin "5") (pinfunction "PB0/PCINT0/AIN0/OC0A/MOSI_5") (pintype "bidirectional"))
    )
    (net (code "70") (name "unconnected-(IC3-PB1{slash}PCINT1{slash}AIN1{slash}OC0B{slash}INT0{slash}MISO-Pad6)") (class "Default")
      (node (ref "IC3") (pin "6") (pinfunction "PB1/PCINT1/AIN1/OC0B/INT0/MISO_6") (pintype "bidirectional"))
    )
    (net (code "71") (name "unconnected-(IC3-PB3{slash}PCINT3{slash}CLKI{slash}ADC3-Pad2)") (class "Default")
      (node (ref "IC3") (pin "2") (pinfunction "PB3/PCINT3/CLKI/ADC3_2") (pintype "bidirectional"))
    )
    (net (code "72") (name "unconnected-(U$2-PadD3)") (class "Default")
      (node (ref "U$2") (pin "D3") (pinfunction "D3_D3") (pintype "bidirectional"))
    )
    (net (code "73") (name "unconnected-(U$2-PadD4)") (class "Default")
      (node (ref "U$2") (pin "D4") (pinfunction "D4_D4") (pintype "bidirectional"))
    )
    (net (code "74") (name "unconnected-(U$2-PadD5)") (class "Default")
      (node (ref "U$2") (pin "D5") (pinfunction "D5_D5") (pintype "bidirectional"))
    )
    (net (code "75") (name "unconnected-(U$2-PadD6)") (class "Default")
      (node (ref "U$2") (pin "D6") (pinfunction "D6_D6") (pintype "bidirectional"))
    )
    (net (code "76") (name "unconnected-(U$2-PadD7)") (class "Default")
      (node (ref "U$2") (pin "D7") (pinfunction "D7_D7") (pintype "bidirectional"))
    )
    (net (code "77") (name "unconnected-(U$2-PadD9)") (class "Default")
      (node (ref "U$2") (pin "D9") (pinfunction "D9_D9") (pintype "bidirectional"))
    )
    (net (code "78") (name "unconnected-(U$2-PadRST)") (class "Default")
      (node (ref "U$2") (pin "RST") (pinfunction "RST_RST") (pintype "bidirectional"))
    )
    (net (code "79") (name "unconnected-(U$2-PadTX0)") (class "Default")
      (node (ref "U$2") (pin "TX0") (pinfunction "TX0_TX0") (pintype "bidirectional"))
    )
    (net (code "80") (name "unconnected-(U$2-PadVCC)") (class "Default")
      (node (ref "U$2") (pin "VCC") (pinfunction "VCC_VCC") (pintype "bidirectional"))
    )
    (net (code "81") (name "unconnected-(U$2-RST2-PadRST1)") (class "Default")
      (node (ref "U$2") (pin "RST1") (pinfunction "RST2_RST1") (pintype "bidirectional"))
    )
    (net (code "82") (name "unconnected-(U$3-Pad5)") (class "Default")
      (node (ref "U$3") (pin "5") (pinfunction "5_5") (pintype "bidirectional"))
    )
    (net (code "83") (name "unconnected-(U$4-Pad5)") (class "Default")
      (node (ref "U$4") (pin "5") (pinfunction "5_5") (pintype "bidirectional"))
    )
    (net (code "84") (name "unconnected-(U5-CLKOUT{slash}SOF-Pad3)") (class "Default")
      (node (ref "U5") (pin "3") (pinfunction "CLKOUT/SOF_3") (pintype "output"))
    )
    (net (code "85") (name "unconnected-(U5-~{INT}-Pad12)") (class "Default")
      (node (ref "U5") (pin "12") (pinfunction "~{INT}_12") (pintype "output"))
    )
    (net (code "86") (name "unconnected-(U5-~{RX0BF}-Pad11)") (class "Default")
      (node (ref "U5") (pin "11") (pinfunction "~{RX0BF}_11") (pintype "output"))
    )
    (net (code "87") (name "unconnected-(U5-~{RX1BF}-Pad10)") (class "Default")
      (node (ref "U5") (pin "10") (pinfunction "~{RX1BF}_10") (pintype "output"))
    )
    (net (code "88") (name "unconnected-(U5-~{TX0RTS}-Pad4)") (class "Default")
      (node (ref "U5") (pin "4") (pinfunction "~{TX0RTS}_4") (pintype "input"))
    )
    (net (code "89") (name "unconnected-(U5-~{TX1RTS}-Pad5)") (class "Default")
      (node (ref "U5") (pin "5") (pinfunction "~{TX1RTS}_5") (pintype "input"))
    )
    (net (code "90") (name "unconnected-(U5-~{TX2RTS}-Pad6)") (class "Default")
      (node (ref "U5") (pin "6") (pinfunction "~{TX2RTS}_6") (pintype "input"))
    )
    (net (code "91") (name "unconnected-(U6-VREF-Pad5)") (class "Default")
      (node (ref "U6") (pin "5") (pinfunction "VREF_5") (pintype "input"))
    )
  )
)
